# Logic.net
KiCad netlist of a schematic drawn in EAGLE
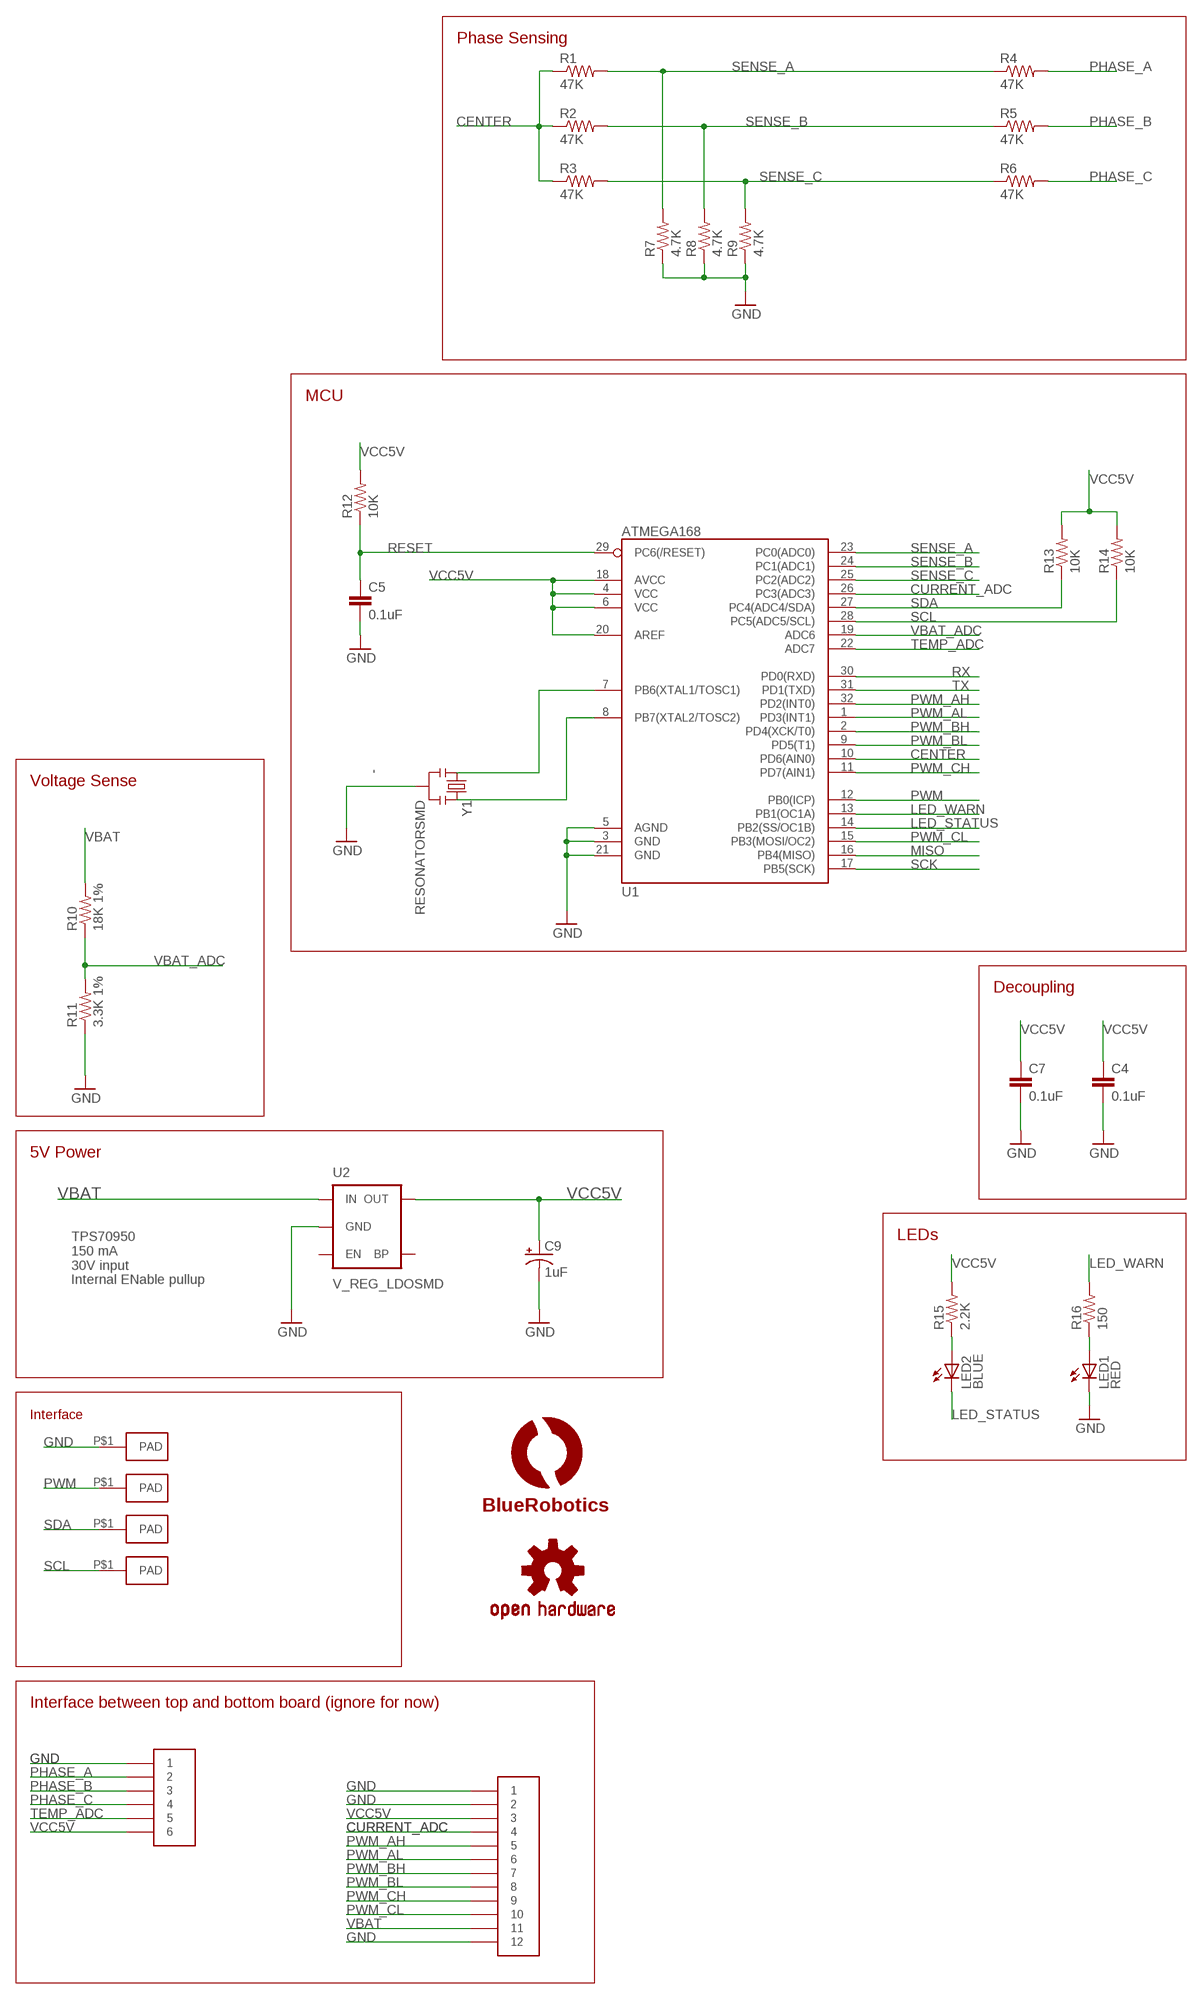
[diagram p0: schematic, sheet 1]

(export (version "E")
  (design (tool "Eeschema 10.0.6"))
  (components
    (comp (ref "C4")
      (value "0.1uF")
      (footprint "eagle-import:0603-CAP")
      (libsource (lib "eagle-import") (part "CAP0603-CAP"))
    )
    (comp (ref "C5")
      (value "0.1uF")
      (footprint "eagle-import:0603-CAP")
      (libsource (lib "eagle-import") (part "CAP0603-CAP"))
    )
    (comp (ref "C7")
      (value "0.1uF")
      (footprint "eagle-import:0603-CAP")
      (libsource (lib "eagle-import") (part "CAP0603-CAP"))
    )
    (comp (ref "C9")
      (value "1uF")
      (footprint "eagle-import:EIA3216")
      (libsource (lib "eagle-import") (part "CAP_POL1206"))
    )
    (comp (ref "LED1")
      (value "RED")
      (footprint "eagle-import:LED3MM")
      (libsource (lib "eagle-import") (part "LED3MM"))
    )
    (comp (ref "LED2")
      (value "BLUE")
      (footprint "eagle-import:LED3MM")
      (libsource (lib "eagle-import") (part "LED3MM"))
    )
    (comp (ref "LOGO1")
      (value "OSHW-LOGOS")
      (footprint "eagle-import:OSHW-LOGO-S")
      (libsource (lib "eagle-import") (part "OSHW-LOGOS"))
    )
    (comp (ref "R1")
      (value "47K")
      (footprint "eagle-import:0603-RES")
      (libsource (lib "eagle-import") (part "33KOHM1/10W1%(0603)"))
    )
    (comp (ref "R2")
      (value "47K")
      (footprint "eagle-import:0603-RES")
      (libsource (lib "eagle-import") (part "33KOHM1/10W1%(0603)"))
    )
    (comp (ref "R3")
      (value "47K")
      (footprint "eagle-import:0603-RES")
      (libsource (lib "eagle-import") (part "33KOHM1/10W1%(0603)"))
    )
    (comp (ref "R4")
      (value "47K")
      (footprint "eagle-import:0603-RES")
      (libsource (lib "eagle-import") (part "33KOHM1/10W1%(0603)"))
    )
    (comp (ref "R5")
      (value "47K")
      (footprint "eagle-import:0603-RES")
      (libsource (lib "eagle-import") (part "33KOHM1/10W1%(0603)"))
    )
    (comp (ref "R6")
      (value "47K")
      (footprint "eagle-import:0603-RES")
      (libsource (lib "eagle-import") (part "33KOHM1/10W1%(0603)"))
    )
    (comp (ref "R7")
      (value "4.7K")
      (footprint "eagle-import:0603-RES")
      (libsource (lib "eagle-import") (part "RESISTOR0603"))
    )
    (comp (ref "R8")
      (value "4.7K")
      (footprint "eagle-import:0603-RES")
      (libsource (lib "eagle-import") (part "RESISTOR0603"))
    )
    (comp (ref "R9")
      (value "4.7K")
      (footprint "eagle-import:0603-RES")
      (libsource (lib "eagle-import") (part "RESISTOR0603"))
    )
    (comp (ref "R10")
      (value "18K 1%")
      (footprint "eagle-import:0603-RES")
      (libsource (lib "eagle-import") (part "33KOHM1/10W1%(0603)"))
    )
    (comp (ref "R11")
      (value "3.3K 1%")
      (footprint "eagle-import:0603-RES")
      (libsource (lib "eagle-import") (part "33KOHM1/10W1%(0603)"))
    )
    (comp (ref "R12")
      (value "10K")
      (footprint "eagle-import:0603-RES")
      (libsource (lib "eagle-import") (part "33KOHM1/10W1%(0603)"))
    )
    (comp (ref "R13")
      (value "10K")
      (footprint "eagle-import:0603-RES")
      (libsource (lib "eagle-import") (part "33KOHM1/10W1%(0603)"))
    )
    (comp (ref "R14")
      (value "10K")
      (footprint "eagle-import:0603-RES")
      (libsource (lib "eagle-import") (part "33KOHM1/10W1%(0603)"))
    )
    (comp (ref "R15")
      (value "2.2K")
      (footprint "eagle-import:0603-RES")
      (libsource (lib "eagle-import") (part "RESISTOR0603-RES"))
    )
    (comp (ref "R16")
      (value "150")
      (footprint "eagle-import:0603-RES")
      (libsource (lib "eagle-import") (part "RESISTOR0603-RES"))
    )
    (comp (ref "U$3")
      (value "PAD1.5X3MM")
      (footprint "eagle-import:PAD-1.5X3MM")
      (libsource (lib "eagle-import") (part "PAD1.5X3MM"))
    )
    (comp (ref "U$4")
      (value "LOGOBR-LOGO-M")
      (footprint "eagle-import:BR-LOGO-MEDIUM")
      (libsource (lib "eagle-import") (part "LOGOBR-LOGO-M"))
    )
    (comp (ref "U$9")
      (value "PAD1.5X3MM")
      (footprint "eagle-import:PAD-1.5X3MM")
      (libsource (lib "eagle-import") (part "PAD1.5X3MM"))
    )
    (comp (ref "U$10")
      (value "PAD1.5X3MM")
      (footprint "eagle-import:PAD-1.5X3MM")
      (libsource (lib "eagle-import") (part "PAD1.5X3MM"))
    )
    (comp (ref "U$11")
      (value "PAD1.5X3MM")
      (footprint "eagle-import:PAD-1.5X3MM")
      (libsource (lib "eagle-import") (part "PAD1.5X3MM"))
    )
    (comp (ref "U$16")
      (value "HEADER-62MM")
      (footprint "eagle-import:HEADER-2MM-6POS")
      (libsource (lib "eagle-import") (part "HEADER-62MM"))
    )
    (comp (ref "U$17")
      (value "HEADER-122MM")
      (footprint "eagle-import:HEADER-2MM-12POS")
      (libsource (lib "eagle-import") (part "HEADER-122MM"))
    )
    (comp (ref "U1")
      (value "ATMEGA168")
      (footprint "eagle-import:TQFP32-08")
      (libsource (lib "eagle-import") (part "ATMEGA168"))
    )
    (comp (ref "U2")
      (value "V_REG_LDOSMD")
      (footprint "eagle-import:SOT23-5")
      (libsource (lib "eagle-import") (part "V_REG_LDOSMD"))
    )
    (comp (ref "Y1")
      (value "RESONATORSMD")
      (footprint "eagle-import:RESONATOR-SMD")
      (libsource (lib "eagle-import") (part "RESONATORSMD"))
    )
  )
  (nets
    (net (code "1") (name "/CENTER") (class "Default")
      (node (ref "R1") (pin "1") (pinfunction "1_1") (pintype "passive"))
      (node (ref "R2") (pin "1") (pinfunction "1_1") (pintype "passive"))
      (node (ref "R3") (pin "1") (pinfunction "1_1") (pintype "passive"))
      (node (ref "U1") (pin "10") (pinfunction "PD6(AIN0)_10") (pintype "bidirectional"))
    )
    (net (code "2") (name "/CURRENT_ADC") (class "Default")
      (node (ref "U$17") (pin "P$4") (pinfunction "4_P$4") (pintype "bidirectional"))
      (node (ref "U1") (pin "26") (pinfunction "PC3(ADC3)_26") (pintype "bidirectional"))
    )
    (net (code "3") (name "/LED_STATUS") (class "Default")
      (node (ref "LED2") (pin "K") (pinfunction "C_K") (pintype "passive"))
      (node (ref "U1") (pin "14") (pinfunction "PB2(SS/OC1B)_14") (pintype "bidirectional"))
    )
    (net (code "4") (name "/LED_WARN") (class "Default")
      (node (ref "R16") (pin "2") (pinfunction "2_2") (pintype "passive"))
      (node (ref "U1") (pin "13") (pinfunction "PB1(OC1A)_13") (pintype "bidirectional"))
    )
    (net (code "5") (name "/MISO") (class "Default")
      (node (ref "U1") (pin "16") (pinfunction "PB4(MISO)_16") (pintype "bidirectional"))
    )
    (net (code "6") (name "/PHASE_A") (class "Default")
      (node (ref "R4") (pin "2") (pinfunction "2_2") (pintype "passive"))
      (node (ref "U$16") (pin "P$2") (pinfunction "2_P$2") (pintype "bidirectional"))
    )
    (net (code "7") (name "/PHASE_B") (class "Default")
      (node (ref "R5") (pin "2") (pinfunction "2_2") (pintype "passive"))
      (node (ref "U$16") (pin "P$3") (pinfunction "3_P$3") (pintype "bidirectional"))
    )
    (net (code "8") (name "/PHASE_C") (class "Default")
      (node (ref "R6") (pin "2") (pinfunction "2_2") (pintype "passive"))
      (node (ref "U$16") (pin "P$4") (pinfunction "4_P$4") (pintype "bidirectional"))
    )
    (net (code "9") (name "/PWM") (class "Default")
      (node (ref "U$11") (pin "P$1") (pinfunction "PAD_P$1") (pintype "bidirectional"))
      (node (ref "U1") (pin "12") (pinfunction "PB0(ICP)_12") (pintype "bidirectional"))
    )
    (net (code "10") (name "/PWM_AH") (class "Default")
      (node (ref "U$17") (pin "P$5") (pinfunction "5_P$5") (pintype "bidirectional"))
      (node (ref "U1") (pin "32") (pinfunction "PD2(INT0)_32") (pintype "bidirectional"))
    )
    (net (code "11") (name "/PWM_AL") (class "Default")
      (node (ref "U$17") (pin "P$6") (pinfunction "6_P$6") (pintype "bidirectional"))
      (node (ref "U1") (pin "1") (pinfunction "PD3(INT1)_1") (pintype "bidirectional"))
    )
    (net (code "12") (name "/PWM_BH") (class "Default")
      (node (ref "U$17") (pin "P$7") (pinfunction "7_P$7") (pintype "bidirectional"))
      (node (ref "U1") (pin "2") (pinfunction "PD4(XCK/T0)_2") (pintype "bidirectional"))
    )
    (net (code "13") (name "/PWM_BL") (class "Default")
      (node (ref "U$17") (pin "P$8") (pinfunction "8_P$8") (pintype "bidirectional"))
      (node (ref "U1") (pin "9") (pinfunction "PD5(T1)_9") (pintype "bidirectional"))
    )
    (net (code "14") (name "/PWM_CH") (class "Default")
      (node (ref "U$17") (pin "P$9") (pinfunction "9_P$9") (pintype "bidirectional"))
      (node (ref "U1") (pin "11") (pinfunction "PD7(AIN1)_11") (pintype "bidirectional"))
    )
    (net (code "15") (name "/PWM_CL") (class "Default")
      (node (ref "U$17") (pin "P$10") (pinfunction "10_P$10") (pintype "bidirectional"))
      (node (ref "U1") (pin "15") (pinfunction "PB3(MOSI/OC2)_15") (pintype "bidirectional"))
    )
    (net (code "16") (name "/RESET") (class "Default")
      (node (ref "C5") (pin "1") (pinfunction "1_1") (pintype "passive"))
      (node (ref "R12") (pin "1") (pinfunction "1_1") (pintype "passive"))
      (node (ref "U1") (pin "29") (pinfunction "PC6(/RESET)_29") (pintype "bidirectional"))
    )
    (net (code "17") (name "/RX") (class "Default")
      (node (ref "U1") (pin "30") (pinfunction "PD0(RXD)_30") (pintype "bidirectional"))
    )
    (net (code "18") (name "/SCK") (class "Default")
      (node (ref "U1") (pin "17") (pinfunction "PB5(SCK)_17") (pintype "bidirectional"))
    )
    (net (code "19") (name "/SCL") (class "Default")
      (node (ref "R14") (pin "1") (pinfunction "1_1") (pintype "passive"))
      (node (ref "U$10") (pin "P$1") (pinfunction "PAD_P$1") (pintype "bidirectional"))
      (node (ref "U1") (pin "28") (pinfunction "PC5(ADC5/SCL)_28") (pintype "bidirectional"))
    )
    (net (code "20") (name "/SDA") (class "Default")
      (node (ref "R13") (pin "1") (pinfunction "1_1") (pintype "passive"))
      (node (ref "U$9") (pin "P$1") (pinfunction "PAD_P$1") (pintype "bidirectional"))
      (node (ref "U1") (pin "27") (pinfunction "PC4(ADC4/SDA)_27") (pintype "bidirectional"))
    )
    (net (code "21") (name "/SENSE_A") (class "Default")
      (node (ref "R1") (pin "2") (pinfunction "2_2") (pintype "passive"))
      (node (ref "R4") (pin "1") (pinfunction "1_1") (pintype "passive"))
      (node (ref "R7") (pin "2") (pinfunction "2_2") (pintype "passive"))
      (node (ref "U1") (pin "23") (pinfunction "PC0(ADC0)_23") (pintype "bidirectional"))
    )
    (net (code "22") (name "/SENSE_B") (class "Default")
      (node (ref "R2") (pin "2") (pinfunction "2_2") (pintype "passive"))
      (node (ref "R5") (pin "1") (pinfunction "1_1") (pintype "passive"))
      (node (ref "R8") (pin "2") (pinfunction "2_2") (pintype "passive"))
      (node (ref "U1") (pin "24") (pinfunction "PC1(ADC1)_24") (pintype "bidirectional"))
    )
    (net (code "23") (name "/SENSE_C") (class "Default")
      (node (ref "R3") (pin "2") (pinfunction "2_2") (pintype "passive"))
      (node (ref "R6") (pin "1") (pinfunction "1_1") (pintype "passive"))
      (node (ref "R9") (pin "2") (pinfunction "2_2") (pintype "passive"))
      (node (ref "U1") (pin "25") (pinfunction "PC2(ADC2)_25") (pintype "bidirectional"))
    )
    (net (code "24") (name "/TEMP_ADC") (class "Default")
      (node (ref "U$16") (pin "P$5") (pinfunction "5_P$5") (pintype "bidirectional"))
      (node (ref "U1") (pin "22") (pinfunction "ADC7_22") (pintype "bidirectional"))
    )
    (net (code "25") (name "/TX") (class "Default")
      (node (ref "U1") (pin "31") (pinfunction "PD1(TXD)_31") (pintype "bidirectional"))
    )
    (net (code "26") (name "/VBAT") (class "Default")
      (node (ref "R10") (pin "2") (pinfunction "2_2") (pintype "passive"))
      (node (ref "U$17") (pin "P$11") (pinfunction "11_P$11") (pintype "bidirectional"))
      (node (ref "U2") (pin "1") (pinfunction "IN_1") (pintype "input"))
    )
    (net (code "27") (name "/VBAT_ADC") (class "Default")
      (node (ref "R10") (pin "1") (pinfunction "1_1") (pintype "passive"))
      (node (ref "R11") (pin "2") (pinfunction "2_2") (pintype "passive"))
      (node (ref "U1") (pin "19") (pinfunction "ADC6_19") (pintype "bidirectional"))
    )
    (net (code "28") (name "/VCC5V") (class "Default")
      (node (ref "C4") (pin "1") (pinfunction "1_1") (pintype "passive"))
      (node (ref "C7") (pin "1") (pinfunction "1_1") (pintype "passive"))
      (node (ref "C9") (pin "A") (pinfunction "+_A") (pintype "passive"))
      (node (ref "R12") (pin "2") (pinfunction "2_2") (pintype "passive"))
      (node (ref "R13") (pin "2") (pinfunction "2_2") (pintype "passive"))
      (node (ref "R14") (pin "2") (pinfunction "2_2") (pintype "passive"))
      (node (ref "R15") (pin "2") (pinfunction "2_2") (pintype "passive"))
      (node (ref "U$16") (pin "P$6") (pinfunction "6_P$6") (pintype "bidirectional"))
      (node (ref "U$17") (pin "P$3") (pinfunction "3_P$3") (pintype "bidirectional"))
      (node (ref "U1") (pin "18") (pinfunction "AVCC_18") (pintype "bidirectional"))
      (node (ref "U1") (pin "20") (pinfunction "AREF_20") (pintype "bidirectional"))
      (node (ref "U1") (pin "4") (pinfunction "VCC_4") (pintype "bidirectional"))
      (node (ref "U1") (pin "6") (pinfunction "VCC_6") (pintype "bidirectional"))
      (node (ref "U2") (pin "5") (pinfunction "OUT_5") (pintype "passive"))
    )
    (net (code "29") (name "GND") (class "Default")
      (node (ref "C4") (pin "2") (pinfunction "2_2") (pintype "passive"))
      (node (ref "C5") (pin "2") (pinfunction "2_2") (pintype "passive"))
      (node (ref "C7") (pin "2") (pinfunction "2_2") (pintype "passive"))
      (node (ref "C9") (pin "C") (pinfunction "-_C") (pintype "passive"))
      (node (ref "LED1") (pin "K") (pinfunction "C_K") (pintype "passive"))
      (node (ref "R11") (pin "1") (pinfunction "1_1") (pintype "passive"))
      (node (ref "R7") (pin "1") (pinfunction "1_1") (pintype "passive"))
      (node (ref "R8") (pin "1") (pinfunction "1_1") (pintype "passive"))
      (node (ref "R9") (pin "1") (pinfunction "1_1") (pintype "passive"))
      (node (ref "U$16") (pin "P$1") (pinfunction "1_P$1") (pintype "bidirectional"))
      (node (ref "U$17") (pin "P$1") (pinfunction "1_P$1") (pintype "bidirectional"))
      (node (ref "U$17") (pin "P$12") (pinfunction "12_P$12") (pintype "bidirectional"))
      (node (ref "U$17") (pin "P$2") (pinfunction "2_P$2") (pintype "bidirectional"))
      (node (ref "U$3") (pin "P$1") (pinfunction "PAD_P$1") (pintype "bidirectional"))
      (node (ref "U1") (pin "21") (pinfunction "GND_21") (pintype "bidirectional"))
      (node (ref "U1") (pin "3") (pinfunction "GND_3") (pintype "bidirectional"))
      (node (ref "U1") (pin "5") (pinfunction "AGND_5") (pintype "bidirectional"))
      (node (ref "U2") (pin "2") (pinfunction "GND_2") (pintype "input"))
      (node (ref "Y1") (pin "2") (pinfunction "2_2") (pintype "passive"))
    )
    (net (code "30") (name "Net-(LED1-PadA)") (class "Default")
      (node (ref "LED1") (pin "A") (pinfunction "A_A") (pintype "passive"))
      (node (ref "R16") (pin "1") (pinfunction "1_1") (pintype "passive"))
    )
    (net (code "31") (name "Net-(LED2-PadA)") (class "Default")
      (node (ref "LED2") (pin "A") (pinfunction "A_A") (pintype "passive"))
      (node (ref "R15") (pin "1") (pinfunction "1_1") (pintype "passive"))
    )
    (net (code "32") (name "Net-(U1-PB6(XTAL1{slash}TOSC1))") (class "Default")
      (node (ref "U1") (pin "7") (pinfunction "PB6(XTAL1/TOSC1)_7") (pintype "bidirectional"))
      (node (ref "Y1") (pin "1") (pinfunction "1_1") (pintype "passive"))
    )
    (net (code "33") (name "Net-(U1-PB7(XTAL2{slash}TOSC2))") (class "Default")
      (node (ref "U1") (pin "8") (pinfunction "PB7(XTAL2/TOSC2)_8") (pintype "bidirectional"))
      (node (ref "Y1") (pin "3") (pinfunction "3_3") (pintype "passive"))
    )
    (net (code "34") (name "unconnected-(U2-BP-Pad4)") (class "Default")
      (node (ref "U2") (pin "4") (pinfunction "BP_4") (pintype "input"))
    )
    (net (code "35") (name "unconnected-(U2-EN-Pad3)") (class "Default")
      (node (ref "U2") (pin "3") (pinfunction "EN_3") (pintype "input"))
    )
  )
)
